# CreeConnectedDriver.net
KiCad netlist of a schematic drawn in EAGLE
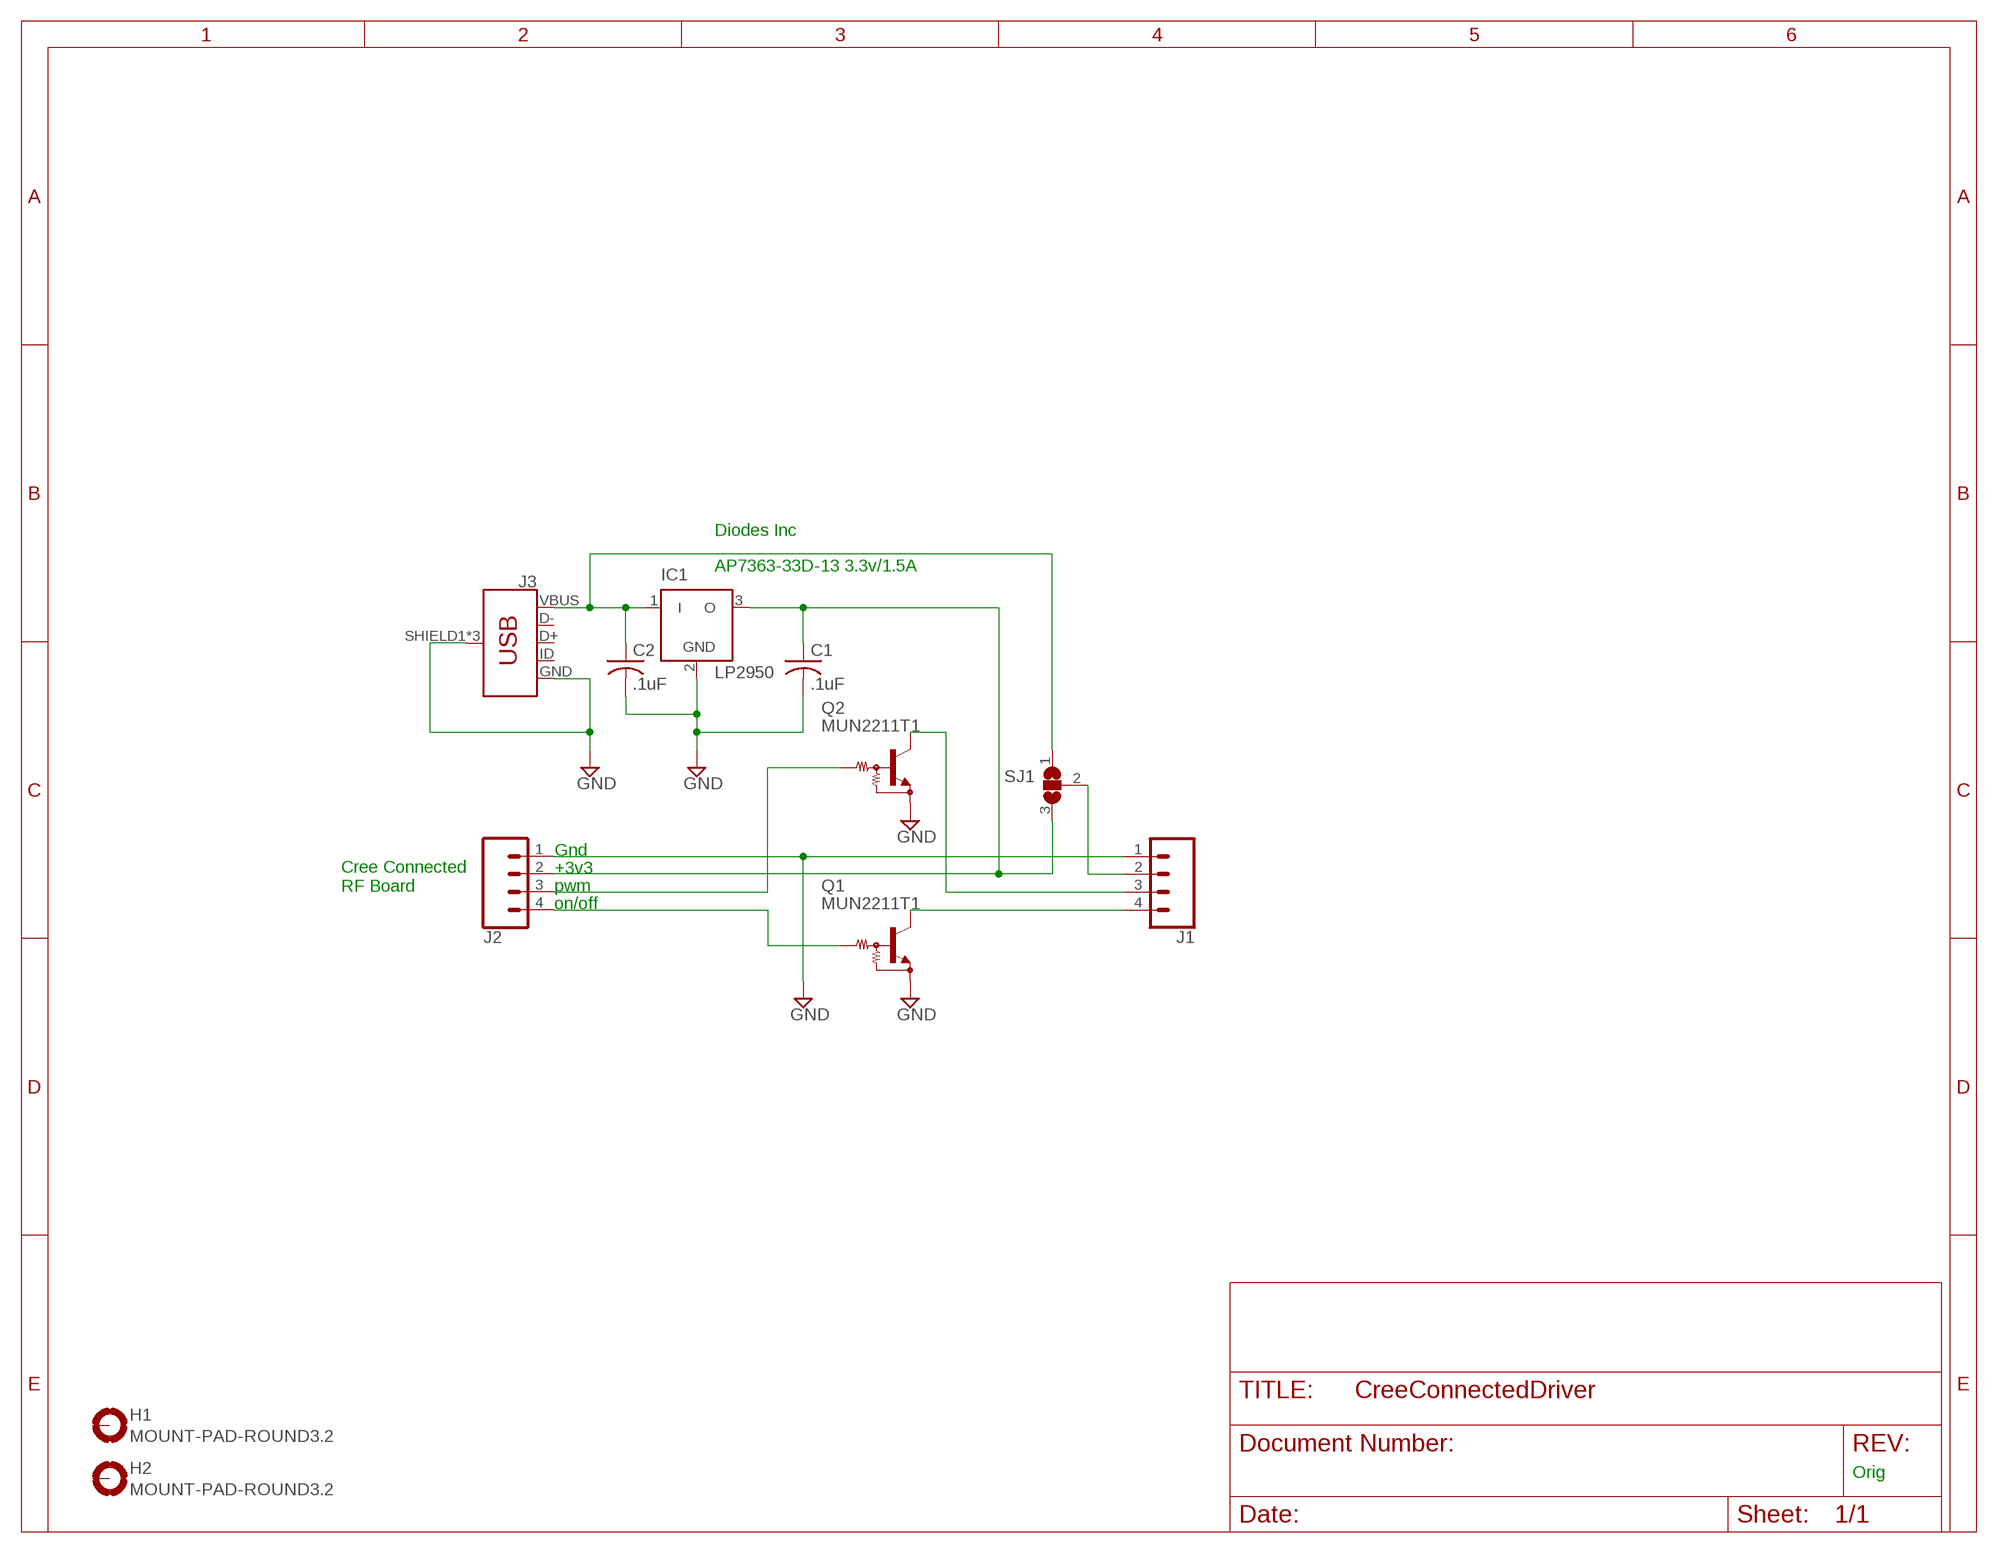
[diagram p0: schematic, sheet 1]

(export (version "E")
  (design (tool "Eeschema 10.0.6"))
  (components
    (comp (ref "C1")
      (value ".1uF")
      (footprint "eagle-import:C1206")
      (libsource (lib "eagle-import") (part "C-USC1206"))
    )
    (comp (ref "C2")
      (value ".1uF")
      (footprint "eagle-import:C1206")
      (libsource (lib "eagle-import") (part "C-USC1206"))
    )
    (comp (ref "H1")
      (value "MOUNT-PAD-ROUND3.2")
      (footprint "eagle-import:3,2-PAD")
      (libsource (lib "eagle-import") (part "MOUNT-PAD-ROUND3.2"))
    )
    (comp (ref "H2")
      (value "MOUNT-PAD-ROUND3.2")
      (footprint "eagle-import:3,2-PAD")
      (libsource (lib "eagle-import") (part "MOUNT-PAD-ROUND3.2"))
    )
    (comp (ref "IC1")
      (value "LP2950")
      (footprint "eagle-import:DPACK")
      (libsource (lib "eagle-import") (part "LP2950"))
    )
    (comp (ref "J1")
      (value "CONN_04JST-PTH-VERT")
      (footprint "eagle-import:JST-4-PTH-VERT")
      (libsource (lib "eagle-import") (part "CONN_04JST-PTH-VERT"))
    )
    (comp (ref "J2")
      (value "CONN_04JST-PTH-VERT")
      (footprint "eagle-import:JST-4-PTH-VERT")
      (libsource (lib "eagle-import") (part "CONN_04JST-PTH-VERT"))
    )
    (comp (ref "J3")
      (value "USB_MICRO-B_FEMALE-SMT")
      (footprint "eagle-import:USB-B-MICRO-SMD")
      (libsource (lib "eagle-import") (part "USB_MICRO-B_FEMALE-SMT"))
    )
    (comp (ref "Q1")
      (value "MUN2211T1")
      (footprint "eagle-import:SC59-BEC")
      (libsource (lib "eagle-import") (part "MUN2211T1"))
    )
    (comp (ref "Q2")
      (value "MUN2211T1")
      (footprint "eagle-import:SC59-BEC")
      (libsource (lib "eagle-import") (part "MUN2211T1"))
    )
    (comp (ref "SJ1")
      (value "SJ2W")
      (footprint "eagle-import:SJ_2")
      (libsource (lib "eagle-import") (part "SJ2W"))
    )
  )
  (nets
    (net (code "1") (name "GND") (class "Default")
      (node (ref "C1") (pin "2") (pinfunction "2_2") (pintype "passive"))
      (node (ref "C2") (pin "2") (pinfunction "2_2") (pintype "passive"))
      (node (ref "IC1") (pin "2") (pinfunction "GND_2") (pintype "power_in"))
      (node (ref "J1") (pin "1") (pinfunction "1_1") (pintype "passive"))
      (node (ref "J2") (pin "1") (pinfunction "1_1") (pintype "passive"))
      (node (ref "J3") (pin "GND") (pinfunction "GND_GND") (pintype "power_in"))
      (node (ref "J3") (pin "SHIELD1") (pinfunction "SHIELD_SHIELD1") (pintype "bidirectional"))
      (node (ref "J3") (pin "SHIELD2") (pinfunction "SHIELD_SHIELD2") (pintype "bidirectional"))
      (node (ref "J3") (pin "SHIELD3") (pinfunction "SHIELD_SHIELD3") (pintype "bidirectional"))
      (node (ref "Q1") (pin "E") (pinfunction "E_E") (pintype "passive"))
      (node (ref "Q2") (pin "E") (pinfunction "E_E") (pintype "passive"))
    )
    (net (code "2") (name "Net-(IC1-I)") (class "Default")
      (node (ref "C2") (pin "1") (pinfunction "1_1") (pintype "passive"))
      (node (ref "IC1") (pin "1") (pinfunction "I_1") (pintype "input"))
      (node (ref "J3") (pin "VBUS") (pinfunction "VBUS_VBUS") (pintype "power_in"))
      (node (ref "SJ1") (pin "1") (pinfunction "1_1") (pintype "passive"))
    )
    (net (code "3") (name "Net-(IC1-O)") (class "Default")
      (node (ref "C1") (pin "1") (pinfunction "1_1") (pintype "passive"))
      (node (ref "IC1") (pin "3") (pinfunction "O_3") (pintype "input"))
      (node (ref "J2") (pin "2") (pinfunction "2_2") (pintype "passive"))
      (node (ref "SJ1") (pin "3") (pinfunction "3_3") (pintype "passive"))
    )
    (net (code "4") (name "Net-(J1-Pad2)") (class "Default")
      (node (ref "J1") (pin "2") (pinfunction "2_2") (pintype "passive"))
      (node (ref "SJ1") (pin "2") (pinfunction "2_2") (pintype "passive"))
    )
    (net (code "5") (name "Net-(J1-Pad3)") (class "Default")
      (node (ref "J1") (pin "3") (pinfunction "3_3") (pintype "passive"))
      (node (ref "Q2") (pin "C") (pinfunction "C_C") (pintype "passive"))
    )
    (net (code "6") (name "Net-(J1-Pad4)") (class "Default")
      (node (ref "J1") (pin "4") (pinfunction "4_4") (pintype "passive"))
      (node (ref "Q1") (pin "C") (pinfunction "C_C") (pintype "passive"))
    )
    (net (code "7") (name "Net-(J2-Pad3)") (class "Default")
      (node (ref "J2") (pin "3") (pinfunction "3_3") (pintype "passive"))
      (node (ref "Q2") (pin "B") (pinfunction "B_B") (pintype "passive"))
    )
    (net (code "8") (name "Net-(J2-Pad4)") (class "Default")
      (node (ref "J2") (pin "4") (pinfunction "4_4") (pintype "passive"))
      (node (ref "Q1") (pin "B") (pinfunction "B_B") (pintype "passive"))
    )
    (net (code "9") (name "unconnected-(H1-MOUNT-PadB3,2)") (class "Default")
      (node (ref "H1") (pin "B3,2") (pinfunction "MOUNT_B3,2") (pintype "passive"))
    )
    (net (code "10") (name "unconnected-(H2-MOUNT-PadB3,2)") (class "Default")
      (node (ref "H2") (pin "B3,2") (pinfunction "MOUNT_B3,2") (pintype "passive"))
    )
    (net (code "11") (name "unconnected-(J3-PadD+)") (class "Default")
      (node (ref "J3") (pin "D+") (pinfunction "D+_D+") (pintype "bidirectional"))
    )
    (net (code "12") (name "unconnected-(J3-PadD-)") (class "Default")
      (node (ref "J3") (pin "D-") (pinfunction "D-_D-") (pintype "bidirectional"))
    )
    (net (code "13") (name "unconnected-(J3-PadID)") (class "Default")
      (node (ref "J3") (pin "ID") (pinfunction "ID_ID") (pintype "bidirectional"))
    )
  )
)
